# old_line_kick.net
KiCad netlist of a schematic drawn in EAGLE
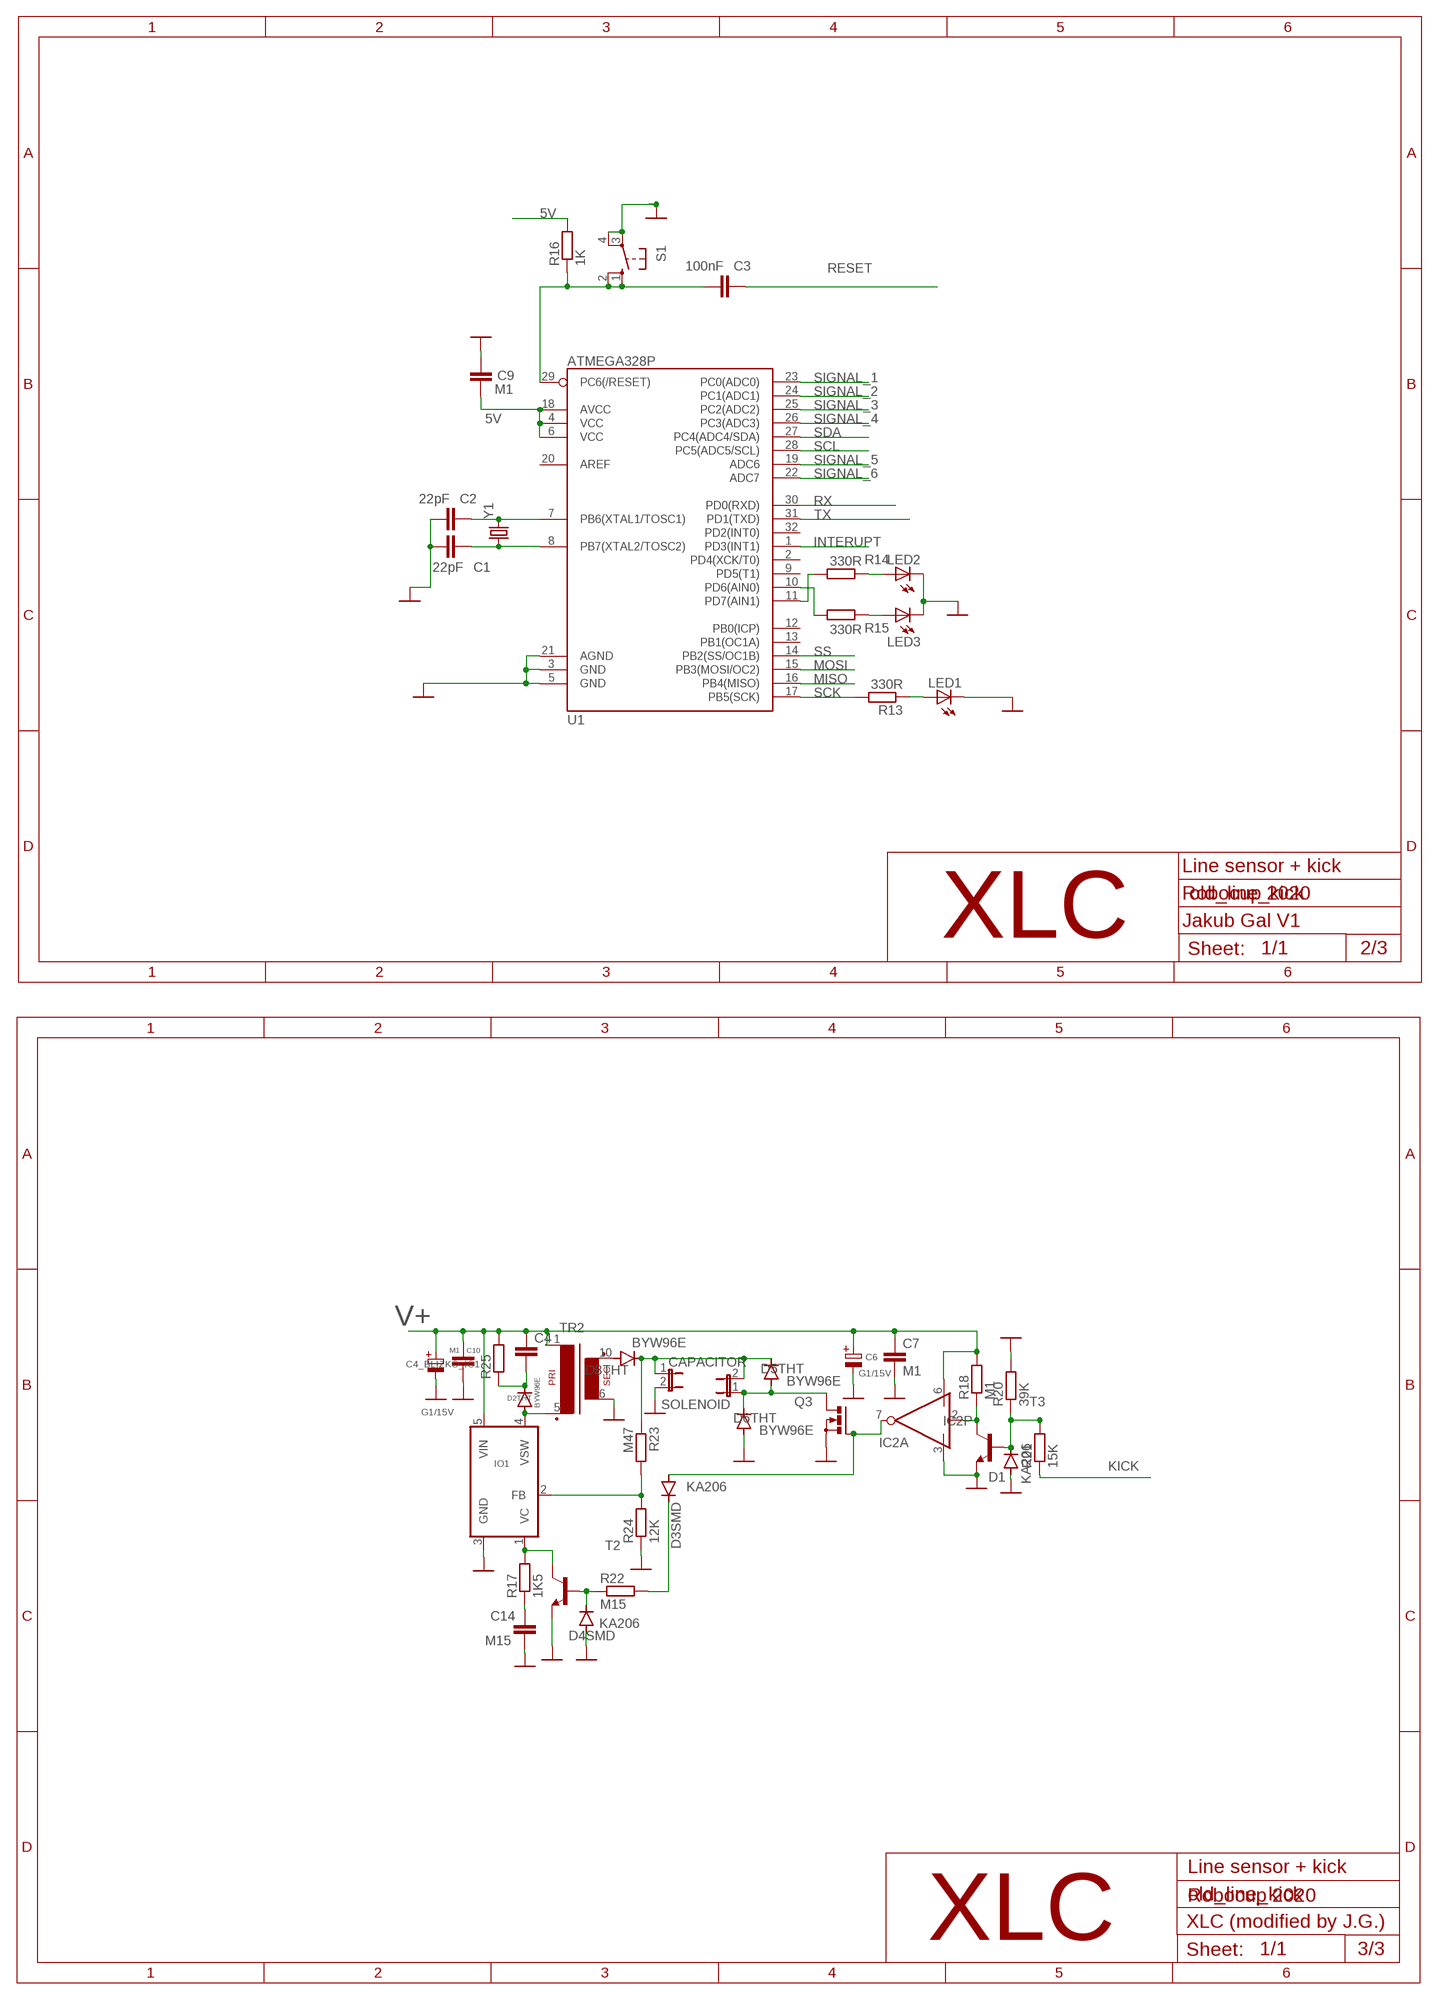
[diagram p0: schematic, sheet 1, part 1 of 2]
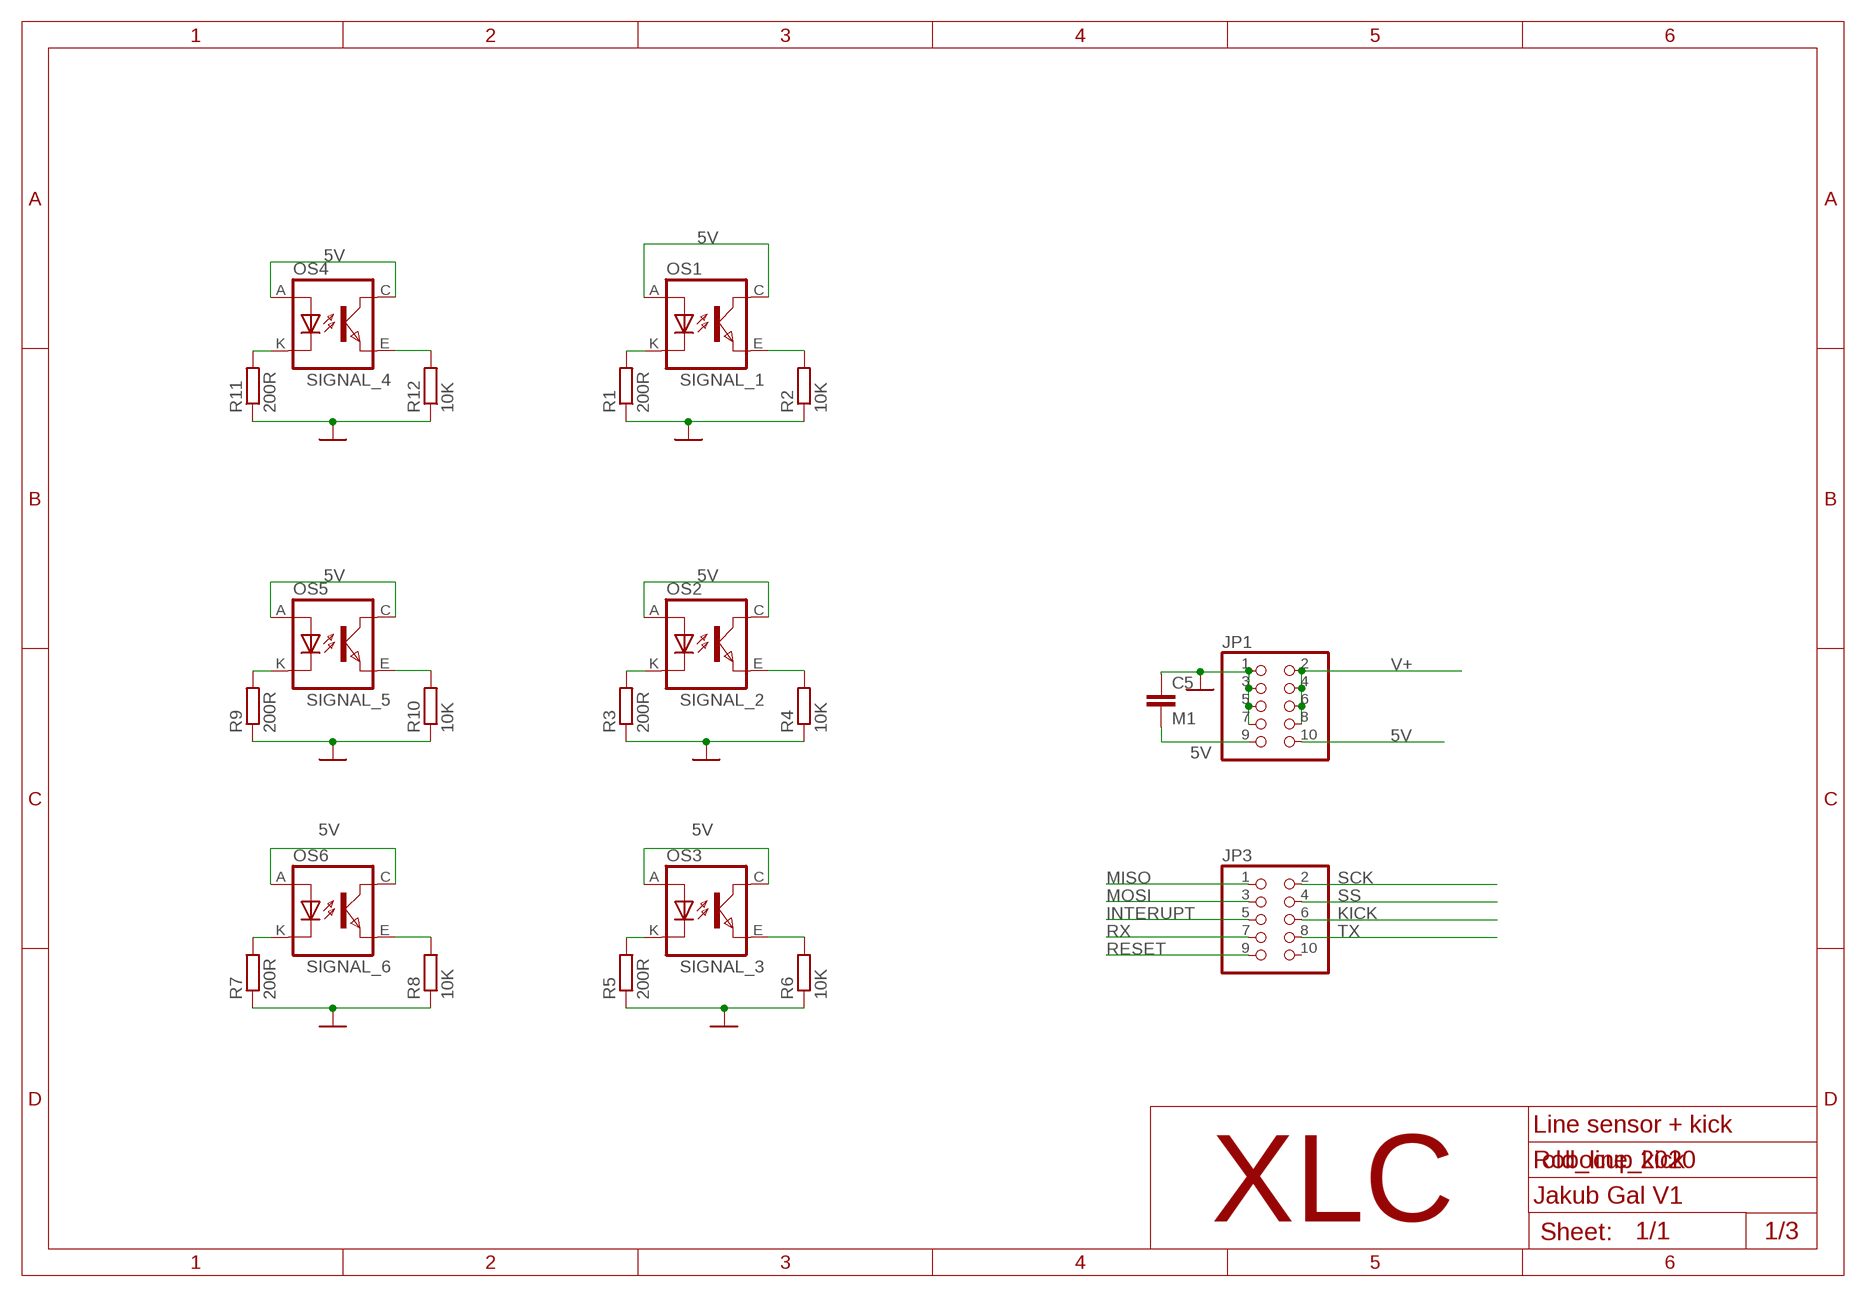
[diagram p1: schematic, sheet 1, part 2 of 2]

(export (version "E")
  (design (tool "Eeschema 10.0.6"))
  (components
    (comp (ref "C1")
      (value "22pF")
      (footprint "eagle-import:C0603")
      (libsource (lib "eagle-import") (part "rcl@1_C-EUC0603"))
    )
    (comp (ref "C2")
      (value "22pF")
      (footprint "eagle-import:C0603")
      (libsource (lib "eagle-import") (part "rcl@1_C-EUC0603"))
    )
    (comp (ref "C3")
      (value "100nF")
      (footprint "eagle-import:C0603")
      (libsource (lib "eagle-import") (part "rcl@1_C-EUC0603"))
    )
    (comp (ref "C4")
      (value "C-EU075-052X106")
      (footprint "eagle-import:C075-052X106")
      (libsource (lib "eagle-import") (part "C-EU075-052X106"))
    )
    (comp (ref "C4_BLIZKO_IO1")
      (value "G1/15V")
      (footprint "eagle-import:E-2,5_7-RAD")
      (libsource (lib "eagle-import") (part "KOND-ELEKT-2,5/7"))
    )
    (comp (ref "C5")
      (value "M1")
      (footprint "eagle-import:C0603")
      (libsource (lib "eagle-import") (part "C-EUC0603"))
    )
    (comp (ref "C6")
      (value "G1/15V")
      (footprint "eagle-import:E-2,5_7-RAD")
      (libsource (lib "eagle-import") (part "KOND-ELEKT-2,5/7"))
    )
    (comp (ref "C7")
      (value "M1")
      (footprint "eagle-import:C0805K")
      (libsource (lib "eagle-import") (part "resistor_C-EUC0805K"))
    )
    (comp (ref "C9")
      (value "M1")
      (footprint "eagle-import:C0603")
      (libsource (lib "eagle-import") (part "rcl@1_C-EUC0603"))
    )
    (comp (ref "C10")
      (value "M1")
      (footprint "eagle-import:C0805K")
      (libsource (lib "eagle-import") (part "resistor_C-EUC0805K"))
    )
    (comp (ref "C14")
      (value "M15")
      (footprint "eagle-import:C0805K")
      (libsource (lib "eagle-import") (part "resistor_C-EUC0805K"))
    )
    (comp (ref "CAPACITOR")
      (value "JP1E")
      (footprint "eagle-import:JP1")
      (libsource (lib "eagle-import") (part "JP1E"))
    )
    (comp (ref "D1")
      (value "KA206")
      (footprint "eagle-import:D-7.5")
      (libsource (lib "eagle-import") (part "DIODE-D-7.5"))
    )
    (comp (ref "D2THT")
      (value "BYW96E")
      (footprint "eagle-import:SOD64-10")
      (libsource (lib "eagle-import") (part "BYW96"))
    )
    (comp (ref "D3SMD")
      (value "KA206")
      (footprint "eagle-import:D-7.5")
      (libsource (lib "eagle-import") (part "DIODE-D-7.5"))
    )
    (comp (ref "D4SMD")
      (value "KA206")
      (footprint "eagle-import:D-7.5")
      (libsource (lib "eagle-import") (part "DIODE-D-7.5"))
    )
    (comp (ref "D5THT")
      (value "BYW96E")
      (footprint "eagle-import:SOD64-10")
      (libsource (lib "eagle-import") (part "BYW96"))
    )
    (comp (ref "D6THT")
      (value "BYW96E")
      (footprint "eagle-import:SOD64-10")
      (libsource (lib "eagle-import") (part "BYW96"))
    )
    (comp (ref "D8THT")
      (value "BYW96E")
      (footprint "eagle-import:SOD64-10")
      (libsource (lib "eagle-import") (part "BYW96"))
    )
    (comp (ref "IC2")
      (value "MIC4423BM")
      (footprint "eagle-import:SO08")
      (libsource (lib "eagle-import") (part "MIC4423BM"))
    )
    (comp (ref "IO1")
      (value "LT1071V")
      (footprint "eagle-import:TO220-5P")
      (libsource (lib "eagle-import") (part "LT1071V"))
    )
    (comp (ref "JP1")
      (value "PINHD-2X5IDC")
      (footprint "eagle-import:2X05_IDC")
      (libsource (lib "eagle-import") (part "PINHD-2X5IDC"))
    )
    (comp (ref "JP3")
      (value "PINHD-2X5IDC")
      (footprint "eagle-import:2X05_IDC")
      (libsource (lib "eagle-import") (part "PINHD-2X5IDC"))
    )
    (comp (ref "LED1")
      (value "LEDCHIPLED_0603")
      (footprint "eagle-import:CHIPLED_0603")
      (libsource (lib "eagle-import") (part "LEDCHIPLED_0603"))
    )
    (comp (ref "LED2")
      (value "LEDCHIPLED_0603")
      (footprint "eagle-import:CHIPLED_0603")
      (libsource (lib "eagle-import") (part "LEDCHIPLED_0603"))
    )
    (comp (ref "LED3")
      (value "LEDCHIPLED_0603")
      (footprint "eagle-import:CHIPLED_0603")
      (libsource (lib "eagle-import") (part "LEDCHIPLED_0603"))
    )
    (comp (ref "OS1")
      (value "TCRT5000")
      (footprint "eagle-import:TCRT5000")
      (libsource (lib "eagle-import") (part "TCRT5000"))
    )
    (comp (ref "OS2")
      (value "TCRT5000")
      (footprint "eagle-import:TCRT5000")
      (libsource (lib "eagle-import") (part "TCRT5000"))
    )
    (comp (ref "OS3")
      (value "TCRT5000")
      (footprint "eagle-import:TCRT5000")
      (libsource (lib "eagle-import") (part "TCRT5000"))
    )
    (comp (ref "OS4")
      (value "TCRT5000")
      (footprint "eagle-import:TCRT5000")
      (fields (field (name "SPICEPREFIX") "O"))
      (libsource (lib "eagle-import") (part "TCRT5000"))
    )
    (comp (ref "OS5")
      (value "TCRT5000")
      (footprint "eagle-import:TCRT5000")
      (libsource (lib "eagle-import") (part "TCRT5000"))
    )
    (comp (ref "OS6")
      (value "TCRT5000")
      (footprint "eagle-import:TCRT5000")
      (fields (field (name "SPICEPREFIX") "O"))
      (libsource (lib "eagle-import") (part "TCRT5000"))
    )
    (comp (ref "Q3")
      (value "PMOSFET_NTO220BV")
      (footprint "eagle-import:TO220BV")
      (libsource (lib "eagle-import") (part "PMOSFET_NTO220BV"))
    )
    (comp (ref "R1")
      (value "200R")
      (footprint "eagle-import:R0603")
      (libsource (lib "eagle-import") (part "R-EU_R0603"))
    )
    (comp (ref "R2")
      (value "10K")
      (footprint "eagle-import:R0603")
      (libsource (lib "eagle-import") (part "R-EU_R0603"))
    )
    (comp (ref "R3")
      (value "200R")
      (footprint "eagle-import:R0603")
      (libsource (lib "eagle-import") (part "R-EU_R0603"))
    )
    (comp (ref "R4")
      (value "10K")
      (footprint "eagle-import:R0603")
      (libsource (lib "eagle-import") (part "R-EU_R0603"))
    )
    (comp (ref "R5")
      (value "200R")
      (footprint "eagle-import:R0603")
      (libsource (lib "eagle-import") (part "R-EU_R0603"))
    )
    (comp (ref "R6")
      (value "10K")
      (footprint "eagle-import:R0603")
      (libsource (lib "eagle-import") (part "R-EU_R0603"))
    )
    (comp (ref "R7")
      (value "200R")
      (footprint "eagle-import:R0603")
      (libsource (lib "eagle-import") (part "R-EU_R0603"))
    )
    (comp (ref "R8")
      (value "10K")
      (footprint "eagle-import:R0603")
      (libsource (lib "eagle-import") (part "R-EU_R0603"))
    )
    (comp (ref "R9")
      (value "200R")
      (footprint "eagle-import:R0603")
      (libsource (lib "eagle-import") (part "R-EU_R0603"))
    )
    (comp (ref "R10")
      (value "10K")
      (footprint "eagle-import:R0603")
      (libsource (lib "eagle-import") (part "R-EU_R0603"))
    )
    (comp (ref "R11")
      (value "200R")
      (footprint "eagle-import:R0603")
      (libsource (lib "eagle-import") (part "R-EU_R0603"))
    )
    (comp (ref "R12")
      (value "10K")
      (footprint "eagle-import:R0603")
      (libsource (lib "eagle-import") (part "R-EU_R0603"))
    )
    (comp (ref "R13")
      (value "330R")
      (footprint "eagle-import:R0603")
      (libsource (lib "eagle-import") (part "R-EU_R0603"))
    )
    (comp (ref "R14")
      (value "330R")
      (footprint "eagle-import:R0603")
      (libsource (lib "eagle-import") (part "R-EU_R0603"))
    )
    (comp (ref "R15")
      (value "330R")
      (footprint "eagle-import:R0603")
      (libsource (lib "eagle-import") (part "R-EU_R0603"))
    )
    (comp (ref "R16")
      (value "1K")
      (footprint "eagle-import:R0603")
      (libsource (lib "eagle-import") (part "R-EU_R0603"))
    )
    (comp (ref "R17")
      (value "1K5")
      (footprint "eagle-import:R1206")
      (libsource (lib "eagle-import") (part "R-EU_R1206"))
    )
    (comp (ref "R18")
      (value "M1")
      (footprint "eagle-import:R1206")
      (libsource (lib "eagle-import") (part "R-EU_R1206"))
    )
    (comp (ref "R20")
      (value "39K")
      (footprint "eagle-import:R1206")
      (libsource (lib "eagle-import") (part "R-EU_R1206"))
    )
    (comp (ref "R21")
      (value "15K")
      (footprint "eagle-import:R1206")
      (libsource (lib "eagle-import") (part "R-EU_R1206"))
    )
    (comp (ref "R22")
      (value "M15")
      (footprint "eagle-import:R1206")
      (libsource (lib "eagle-import") (part "R-EU_R1206"))
    )
    (comp (ref "R23")
      (value "M47")
      (footprint "eagle-import:R1206")
      (libsource (lib "eagle-import") (part "R-EU_R1206"))
    )
    (comp (ref "R24")
      (value "12K")
      (footprint "eagle-import:R1206")
      (libsource (lib "eagle-import") (part "R-EU_R1206"))
    )
    (comp (ref "R25")
      (value "REZISTOR-7,5MM-HORIZ")
      (footprint "eagle-import:R-7,5H")
      (libsource (lib "eagle-import") (part "REZISTOR-7,5MM-HORIZ"))
    )
    (comp (ref "S1")
      (value "10-XX")
      (footprint "eagle-import:B3F-10XX")
      (fields (field (name "MPN") "B3F-1000"))
      (libsource (lib "eagle-import") (part "10-XX"))
    )
    (comp (ref "SOLENOID")
      (value "JP1E")
      (footprint "eagle-import:JP1")
      (libsource (lib "eagle-import") (part "JP1E"))
    )
    (comp (ref "T2")
      (value "-NPN-SC59-BEC")
      (footprint "eagle-import:SC59-BEC")
      (libsource (lib "eagle-import") (part "-NPN-SC59-BEC"))
    )
    (comp (ref "T3")
      (value "-NPN-SC59-BEC")
      (footprint "eagle-import:SC59-BEC")
      (libsource (lib "eagle-import") (part "-NPN-SC59-BEC"))
    )
    (comp (ref "TR2")
      (value "TRAFO-E10-R\"\"")
      (footprint "eagle-import:TRAFO-EE17X20")
      (libsource (lib "eagle-import") (part "TRAFO-E10-R{dblquote}{dblquote}"))
    )
    (comp (ref "U1")
      (value "ATMEGA328P")
      (footprint "eagle-import:TQFP32-08")
      (libsource (lib "eagle-import") (part "ATMEGA328_SMT"))
    )
    (comp (ref "Y1")
      (value "CRYSTALHC49US")
      (footprint "eagle-import:HC49US")
      (libsource (lib "eagle-import") (part "CRYSTALHC49US"))
    )
  )
  (nets
    (net (code "1") (name "/5V") (class "Default")
      (node (ref "C5") (pin "2") (pinfunction "2_2") (pintype "passive"))
      (node (ref "C9") (pin "1") (pinfunction "1_1") (pintype "passive"))
      (node (ref "JP1") (pin "10") (pinfunction "10_10") (pintype "passive"))
      (node (ref "JP1") (pin "9") (pinfunction "9_9") (pintype "passive"))
      (node (ref "OS1") (pin "A") (pinfunction "ANODE_A") (pintype "passive"))
      (node (ref "OS1") (pin "C") (pinfunction "COLLECTOR_C") (pintype "passive"))
      (node (ref "OS2") (pin "A") (pinfunction "ANODE_A") (pintype "passive"))
      (node (ref "OS2") (pin "C") (pinfunction "COLLECTOR_C") (pintype "passive"))
      (node (ref "OS3") (pin "A") (pinfunction "ANODE_A") (pintype "passive"))
      (node (ref "OS3") (pin "C") (pinfunction "COLLECTOR_C") (pintype "passive"))
      (node (ref "OS4") (pin "A") (pinfunction "ANODE_A") (pintype "passive"))
      (node (ref "OS4") (pin "C") (pinfunction "COLLECTOR_C") (pintype "passive"))
      (node (ref "OS5") (pin "A") (pinfunction "ANODE_A") (pintype "passive"))
      (node (ref "OS5") (pin "C") (pinfunction "COLLECTOR_C") (pintype "passive"))
      (node (ref "OS6") (pin "A") (pinfunction "ANODE_A") (pintype "passive"))
      (node (ref "OS6") (pin "C") (pinfunction "COLLECTOR_C") (pintype "passive"))
      (node (ref "R16") (pin "2") (pinfunction "2_2") (pintype "passive"))
      (node (ref "U1") (pin "18") (pinfunction "AVCC_18") (pintype "bidirectional"))
      (node (ref "U1") (pin "4") (pinfunction "VCC_4") (pintype "bidirectional"))
      (node (ref "U1") (pin "6") (pinfunction "VCC_6") (pintype "bidirectional"))
    )
    (net (code "2") (name "/INTERUPT") (class "Default")
      (node (ref "JP3") (pin "5") (pinfunction "5_5") (pintype "passive"))
      (node (ref "U1") (pin "1") (pinfunction "PD3(INT1)_1") (pintype "bidirectional"))
    )
    (net (code "3") (name "/KICK") (class "Default")
      (node (ref "JP3") (pin "6") (pinfunction "6_6") (pintype "passive"))
      (node (ref "R21") (pin "1") (pinfunction "1_1") (pintype "passive"))
    )
    (net (code "4") (name "/MISO") (class "Default")
      (node (ref "JP3") (pin "1") (pinfunction "1_1") (pintype "passive"))
      (node (ref "U1") (pin "16") (pinfunction "PB4(MISO)_16") (pintype "bidirectional"))
    )
    (net (code "5") (name "/MOSI") (class "Default")
      (node (ref "JP3") (pin "3") (pinfunction "3_3") (pintype "passive"))
      (node (ref "U1") (pin "15") (pinfunction "PB3(MOSI/OC2)_15") (pintype "bidirectional"))
    )
    (net (code "6") (name "/RESET") (class "Default")
      (node (ref "C3") (pin "2") (pinfunction "2_2") (pintype "passive"))
      (node (ref "JP3") (pin "9") (pinfunction "9_9") (pintype "passive"))
    )
    (net (code "7") (name "/RX") (class "Default")
      (node (ref "JP3") (pin "7") (pinfunction "7_7") (pintype "passive"))
      (node (ref "U1") (pin "30") (pinfunction "PD0(RXD)_30") (pintype "bidirectional"))
    )
    (net (code "8") (name "/SCK") (class "Default")
      (node (ref "JP3") (pin "2") (pinfunction "2_2") (pintype "passive"))
      (node (ref "R13") (pin "2") (pinfunction "2_2") (pintype "passive"))
      (node (ref "U1") (pin "17") (pinfunction "PB5(SCK)_17") (pintype "bidirectional"))
    )
    (net (code "9") (name "/SCL") (class "Default")
      (node (ref "U1") (pin "28") (pinfunction "PC5(ADC5/SCL)_28") (pintype "bidirectional"))
    )
    (net (code "10") (name "/SDA") (class "Default")
      (node (ref "U1") (pin "27") (pinfunction "PC4(ADC4/SDA)_27") (pintype "bidirectional"))
    )
    (net (code "11") (name "/SIGNAL_1") (class "Default")
      (node (ref "OS1") (pin "E") (pinfunction "EMITTER_E") (pintype "passive"))
      (node (ref "R2") (pin "2") (pinfunction "2_2") (pintype "passive"))
      (node (ref "U1") (pin "23") (pinfunction "PC0(ADC0)_23") (pintype "bidirectional"))
    )
    (net (code "12") (name "/SIGNAL_2") (class "Default")
      (node (ref "OS2") (pin "E") (pinfunction "EMITTER_E") (pintype "passive"))
      (node (ref "R4") (pin "2") (pinfunction "2_2") (pintype "passive"))
      (node (ref "U1") (pin "24") (pinfunction "PC1(ADC1)_24") (pintype "bidirectional"))
    )
    (net (code "13") (name "/SIGNAL_3") (class "Default")
      (node (ref "OS3") (pin "E") (pinfunction "EMITTER_E") (pintype "passive"))
      (node (ref "R6") (pin "2") (pinfunction "2_2") (pintype "passive"))
      (node (ref "U1") (pin "25") (pinfunction "PC2(ADC2)_25") (pintype "bidirectional"))
    )
    (net (code "14") (name "/SIGNAL_4") (class "Default")
      (node (ref "OS4") (pin "E") (pinfunction "EMITTER_E") (pintype "passive"))
      (node (ref "R12") (pin "2") (pinfunction "2_2") (pintype "passive"))
      (node (ref "U1") (pin "26") (pinfunction "PC3(ADC3)_26") (pintype "bidirectional"))
    )
    (net (code "15") (name "/SIGNAL_5") (class "Default")
      (node (ref "OS5") (pin "E") (pinfunction "EMITTER_E") (pintype "passive"))
      (node (ref "R10") (pin "2") (pinfunction "2_2") (pintype "passive"))
      (node (ref "U1") (pin "19") (pinfunction "ADC6_19") (pintype "bidirectional"))
    )
    (net (code "16") (name "/SIGNAL_6") (class "Default")
      (node (ref "OS6") (pin "E") (pinfunction "EMITTER_E") (pintype "passive"))
      (node (ref "R8") (pin "2") (pinfunction "2_2") (pintype "passive"))
      (node (ref "U1") (pin "22") (pinfunction "ADC7_22") (pintype "bidirectional"))
    )
    (net (code "17") (name "/SS") (class "Default")
      (node (ref "JP3") (pin "4") (pinfunction "4_4") (pintype "passive"))
      (node (ref "U1") (pin "14") (pinfunction "PB2(SS/OC1B)_14") (pintype "bidirectional"))
    )
    (net (code "18") (name "/TX") (class "Default")
      (node (ref "JP3") (pin "8") (pinfunction "8_8") (pintype "passive"))
      (node (ref "U1") (pin "31") (pinfunction "PD1(TXD)_31") (pintype "bidirectional"))
    )
    (net (code "19") (name "/V+") (class "Default")
      (node (ref "C10") (pin "1") (pinfunction "1_1") (pintype "passive"))
      (node (ref "C4") (pin "1") (pinfunction "1_1") (pintype "passive"))
      (node (ref "C4_BLIZKO_IO1") (pin "+") (pinfunction "+_+") (pintype "passive"))
      (node (ref "C6") (pin "+") (pinfunction "+_+") (pintype "passive"))
      (node (ref "C7") (pin "1") (pinfunction "1_1") (pintype "passive"))
      (node (ref "IC2") (pin "6") (pinfunction "V+_6") (pintype "power_in"))
      (node (ref "IO1") (pin "5") (pinfunction "VIN_5") (pintype "power_in"))
      (node (ref "JP1") (pin "2") (pinfunction "2_2") (pintype "passive"))
      (node (ref "JP1") (pin "4") (pinfunction "4_4") (pintype "passive"))
      (node (ref "JP1") (pin "6") (pinfunction "6_6") (pintype "passive"))
      (node (ref "JP1") (pin "8") (pinfunction "8_8") (pintype "passive"))
      (node (ref "R18") (pin "2") (pinfunction "2_2") (pintype "passive"))
      (node (ref "R25") (pin "2") (pinfunction "2_2") (pintype "passive"))
      (node (ref "TR2") (pin "1") (pinfunction "1_1") (pintype "passive"))
    )
    (net (code "20") (name "GND") (class "Default")
      (node (ref "C1") (pin "1") (pinfunction "1_1") (pintype "passive"))
      (node (ref "C10") (pin "2") (pinfunction "2_2") (pintype "passive"))
      (node (ref "C14") (pin "2") (pinfunction "2_2") (pintype "passive"))
      (node (ref "C2") (pin "1") (pinfunction "1_1") (pintype "passive"))
      (node (ref "C4_BLIZKO_IO1") (pin "-") (pinfunction "-_-") (pintype "passive"))
      (node (ref "C5") (pin "1") (pinfunction "1_1") (pintype "passive"))
      (node (ref "C6") (pin "-") (pinfunction "-_-") (pintype "passive"))
      (node (ref "C7") (pin "2") (pinfunction "2_2") (pintype "passive"))
      (node (ref "C9") (pin "2") (pinfunction "2_2") (pintype "passive"))
      (node (ref "CAPACITOR") (pin "2") (pinfunction "2_2") (pintype "passive"))
      (node (ref "D1") (pin "A") (pinfunction "A_A") (pintype "passive"))
      (node (ref "D4SMD") (pin "A") (pinfunction "A_A") (pintype "passive"))
      (node (ref "D6THT") (pin "A") (pinfunction "A_A") (pintype "passive"))
      (node (ref "IC2") (pin "3") (pinfunction "GND_3") (pintype "power_in"))
      (node (ref "IO1") (pin "3") (pinfunction "GND_3") (pintype "power_in"))
      (node (ref "JP1") (pin "1") (pinfunction "1_1") (pintype "passive"))
      (node (ref "JP1") (pin "3") (pinfunction "3_3") (pintype "passive"))
      (node (ref "JP1") (pin "5") (pinfunction "5_5") (pintype "passive"))
      (node (ref "JP1") (pin "7") (pinfunction "7_7") (pintype "passive"))
      (node (ref "LED1") (pin "C") (pinfunction "C_C") (pintype "passive"))
      (node (ref "LED2") (pin "C") (pinfunction "C_C") (pintype "passive"))
      (node (ref "LED3") (pin "C") (pinfunction "C_C") (pintype "passive"))
      (node (ref "Q3") (pin "S") (pinfunction "S_S") (pintype "passive"))
      (node (ref "R1") (pin "1") (pinfunction "1_1") (pintype "passive"))
      (node (ref "R10") (pin "1") (pinfunction "1_1") (pintype "passive"))
      (node (ref "R11") (pin "1") (pinfunction "1_1") (pintype "passive"))
      (node (ref "R12") (pin "1") (pinfunction "1_1") (pintype "passive"))
      (node (ref "R2") (pin "1") (pinfunction "1_1") (pintype "passive"))
      (node (ref "R20") (pin "2") (pinfunction "2_2") (pintype "passive"))
      (node (ref "R24") (pin "1") (pinfunction "1_1") (pintype "passive"))
      (node (ref "R3") (pin "1") (pinfunction "1_1") (pintype "passive"))
      (node (ref "R4") (pin "1") (pinfunction "1_1") (pintype "passive"))
      (node (ref "R5") (pin "1") (pinfunction "1_1") (pintype "passive"))
      (node (ref "R6") (pin "1") (pinfunction "1_1") (pintype "passive"))
      (node (ref "R7") (pin "1") (pinfunction "1_1") (pintype "passive"))
      (node (ref "R8") (pin "1") (pinfunction "1_1") (pintype "passive"))
      (node (ref "R9") (pin "1") (pinfunction "1_1") (pintype "passive"))
      (node (ref "S1") (pin "3") (pinfunction "P_3") (pintype "passive"))
      (node (ref "S1") (pin "4") (pinfunction "P1_4") (pintype "passive"))
      (node (ref "T2") (pin "E") (pinfunction "E_E") (pintype "passive"))
      (node (ref "T3") (pin "E") (pinfunction "E_E") (pintype "passive"))
      (node (ref "TR2") (pin "6") (pinfunction "3_6") (pintype "passive"))
      (node (ref "U1") (pin "21") (pinfunction "AGND_21") (pintype "bidirectional"))
      (node (ref "U1") (pin "3") (pinfunction "GND_3") (pintype "bidirectional"))
      (node (ref "U1") (pin "5") (pinfunction "GND_5") (pintype "bidirectional"))
    )
    (net (code "21") (name "Net-(C4-Pad2)") (class "Default")
      (node (ref "C4") (pin "2") (pinfunction "2_2") (pintype "passive"))
      (node (ref "D2THT") (pin "C") (pinfunction "C_C") (pintype "passive"))
      (node (ref "R25") (pin "1") (pinfunction "1_1") (pintype "passive"))
    )
    (net (code "22") (name "Net-(C14-Pad1)") (class "Default")
      (node (ref "C14") (pin "1") (pinfunction "1_1") (pintype "passive"))
      (node (ref "R17") (pin "1") (pinfunction "1_1") (pintype "passive"))
    )
    (net (code "23") (name "Net-(CAPACITOR-Pad1)") (class "Default")
      (node (ref "CAPACITOR") (pin "1") (pinfunction "1_1") (pintype "passive"))
      (node (ref "D5THT") (pin "C") (pinfunction "C_C") (pintype "passive"))
      (node (ref "D8THT") (pin "C") (pinfunction "C_C") (pintype "passive"))
      (node (ref "R23") (pin "1") (pinfunction "1_1") (pintype "passive"))
      (node (ref "SOLENOID") (pin "2") (pinfunction "2_2") (pintype "passive"))
    )
    (net (code "24") (name "Net-(D1-PadC)") (class "Default")
      (node (ref "D1") (pin "C") (pinfunction "C_C") (pintype "passive"))
      (node (ref "R20") (pin "1") (pinfunction "1_1") (pintype "passive"))
      (node (ref "R21") (pin "2") (pinfunction "2_2") (pintype "passive"))
      (node (ref "T3") (pin "B") (pinfunction "B_B") (pintype "passive"))
    )
    (net (code "25") (name "Net-(D3SMD-PadC)") (class "Default")
      (node (ref "D3SMD") (pin "C") (pinfunction "C_C") (pintype "passive"))
      (node (ref "R22") (pin "2") (pinfunction "2_2") (pintype "passive"))
    )
    (net (code "26") (name "Net-(D4SMD-PadC)") (class "Default")
      (node (ref "D4SMD") (pin "C") (pinfunction "C_C") (pintype "passive"))
      (node (ref "R22") (pin "1") (pinfunction "1_1") (pintype "passive"))
      (node (ref "T2") (pin "B") (pinfunction "B_B") (pintype "passive"))
    )
    (net (code "27") (name "Net-(D5THT-PadA)") (class "Default")
      (node (ref "D5THT") (pin "A") (pinfunction "A_A") (pintype "passive"))
      (node (ref "D6THT") (pin "C") (pinfunction "C_C") (pintype "passive"))
      (node (ref "Q3") (pin "D") (pinfunction "D_D") (pintype "passive"))
      (node (ref "SOLENOID") (pin "1") (pinfunction "1_1") (pintype "passive"))
    )
    (net (code "28") (name "Net-(IC2A-IN)") (class "Default")
      (node (ref "IC2") (pin "2") (pinfunction "IN_2") (pintype "input"))
      (node (ref "R18") (pin "1") (pinfunction "1_1") (pintype "passive"))
      (node (ref "T3") (pin "C") (pinfunction "C_C") (pintype "passive"))
    )
    (net (code "29") (name "Net-(IC2A-OUT)") (class "Default")
      (node (ref "D3SMD") (pin "A") (pinfunction "A_A") (pintype "passive"))
      (node (ref "IC2") (pin "7") (pinfunction "OUT_7") (pintype "output"))
      (node (ref "Q3") (pin "G") (pinfunction "G_G") (pintype "passive"))
    )
    (net (code "30") (name "Net-(IO1-FB)") (class "Default")
      (node (ref "IO1") (pin "2") (pinfunction "FB_2") (pintype "input"))
      (node (ref "R23") (pin "2") (pinfunction "2_2") (pintype "passive"))
      (node (ref "R24") (pin "2") (pinfunction "2_2") (pintype "passive"))
    )
    (net (code "31") (name "Net-(IO1-VC)") (class "Default")
      (node (ref "IO1") (pin "1") (pinfunction "VC_1") (pintype "input"))
      (node (ref "R17") (pin "2") (pinfunction "2_2") (pintype "passive"))
      (node (ref "T2") (pin "C") (pinfunction "C_C") (pintype "passive"))
    )
    (net (code "32") (name "Net-(IO1-VSW)") (class "Default")
      (node (ref "D2THT") (pin "A") (pinfunction "A_A") (pintype "passive"))
      (node (ref "IO1") (pin "4") (pinfunction "VSW_4") (pintype "output"))
      (node (ref "TR2") (pin "5") (pinfunction "2_5") (pintype "passive"))
    )
    (net (code "33") (name "Net-(LED1-PadA)") (class "Default")
      (node (ref "LED1") (pin "A") (pinfunction "A_A") (pintype "passive"))
      (node (ref "R13") (pin "1") (pinfunction "1_1") (pintype "passive"))
    )
    (net (code "34") (name "Net-(LED2-PadA)") (class "Default")
      (node (ref "LED2") (pin "A") (pinfunction "A_A") (pintype "passive"))
      (node (ref "R14") (pin "1") (pinfunction "1_1") (pintype "passive"))
    )
    (net (code "35") (name "Net-(LED3-PadA)") (class "Default")
      (node (ref "LED3") (pin "A") (pinfunction "A_A") (pintype "passive"))
      (node (ref "R15") (pin "1") (pinfunction "1_1") (pintype "passive"))
    )
    (net (code "36") (name "Net-(OS1-CATHODE)") (class "Default")
      (node (ref "OS1") (pin "K") (pinfunction "CATHODE_K") (pintype "passive"))
      (node (ref "R1") (pin "2") (pinfunction "2_2") (pintype "passive"))
    )
    (net (code "37") (name "Net-(OS2-CATHODE)") (class "Default")
      (node (ref "OS2") (pin "K") (pinfunction "CATHODE_K") (pintype "passive"))
      (node (ref "R3") (pin "2") (pinfunction "2_2") (pintype "passive"))
    )
    (net (code "38") (name "Net-(OS3-CATHODE)") (class "Default")
      (node (ref "OS3") (pin "K") (pinfunction "CATHODE_K") (pintype "passive"))
      (node (ref "R5") (pin "2") (pinfunction "2_2") (pintype "passive"))
    )
    (net (code "39") (name "Net-(OS4-CATHODE)") (class "Default")
      (node (ref "OS4") (pin "K") (pinfunction "CATHODE_K") (pintype "passive"))
      (node (ref "R11") (pin "2") (pinfunction "2_2") (pintype "passive"))
    )
    (net (code "40") (name "Net-(OS5-CATHODE)") (class "Default")
      (node (ref "OS5") (pin "K") (pinfunction "CATHODE_K") (pintype "passive"))
      (node (ref "R9") (pin "2") (pinfunction "2_2") (pintype "passive"))
    )
    (net (code "41") (name "Net-(OS6-CATHODE)") (class "Default")
      (node (ref "OS6") (pin "K") (pinfunction "CATHODE_K") (pintype "passive"))
      (node (ref "R7") (pin "2") (pinfunction "2_2") (pintype "passive"))
    )
    (net (code "42") (name "Net-(S1-S)") (class "Default")
      (node (ref "C3") (pin "1") (pinfunction "1_1") (pintype "passive"))
      (node (ref "R16") (pin "1") (pinfunction "1_1") (pintype "passive"))
      (node (ref "S1") (pin "1") (pinfunction "S_1") (pintype "passive"))
      (node (ref "S1") (pin "2") (pinfunction "S1_2") (pintype "passive"))
      (node (ref "U1") (pin "29") (pinfunction "PC6(/RESET)_29") (pintype "bidirectional"))
    )
    (net (code "43") (name "Net-(TR2-4)") (class "Default")
      (node (ref "D8THT") (pin "A") (pinfunction "A_A") (pintype "passive"))
      (node (ref "TR2") (pin "10") (pinfunction "4_10") (pintype "passive"))
    )
    (net (code "44") (name "Net-(U1-PB6(XTAL1{slash}TOSC1))") (class "Default")
      (node (ref "C2") (pin "2") (pinfunction "2_2") (pintype "passive"))
      (node (ref "U1") (pin "7") (pinfunction "PB6(XTAL1/TOSC1)_7") (pintype "bidirectional"))
      (node (ref "Y1") (pin "2") (pinfunction "2_2") (pintype "passive"))
    )
    (net (code "45") (name "Net-(U1-PB7(XTAL2{slash}TOSC2))") (class "Default")
      (node (ref "C1") (pin "2") (pinfunction "2_2") (pintype "passive"))
      (node (ref "U1") (pin "8") (pinfunction "PB7(XTAL2/TOSC2)_8") (pintype "bidirectional"))
      (node (ref "Y1") (pin "1") (pinfunction "1_1") (pintype "passive"))
    )
    (net (code "46") (name "Net-(U1-PD6(AIN0))") (class "Default")
      (node (ref "R15") (pin "2") (pinfunction "2_2") (pintype "passive"))
      (node (ref "U1") (pin "10") (pinfunction "PD6(AIN0)_10") (pintype "bidirectional"))
    )
    (net (code "47") (name "Net-(U1-PD7(AIN1))") (class "Default")
      (node (ref "R14") (pin "2") (pinfunction "2_2") (pintype "passive"))
      (node (ref "U1") (pin "11") (pinfunction "PD7(AIN1)_11") (pintype "bidirectional"))
    )
    (net (code "48") (name "unconnected-(JP3-Pad10)") (class "Default")
      (node (ref "JP3") (pin "10") (pinfunction "10_10") (pintype "passive"))
    )
    (net (code "49") (name "unconnected-(U1-AREF-Pad20)") (class "Default")
      (node (ref "U1") (pin "20") (pinfunction "AREF_20") (pintype "bidirectional"))
    )
    (net (code "50") (name "unconnected-(U1-PB0(ICP)-Pad12)") (class "Default")
      (node (ref "U1") (pin "12") (pinfunction "PB0(ICP)_12") (pintype "bidirectional"))
    )
    (net (code "51") (name "unconnected-(U1-PB1(OC1A)-Pad13)") (class "Default")
      (node (ref "U1") (pin "13") (pinfunction "PB1(OC1A)_13") (pintype "bidirectional"))
    )
    (net (code "52") (name "unconnected-(U1-PD2(INT0)-Pad32)") (class "Default")
      (node (ref "U1") (pin "32") (pinfunction "PD2(INT0)_32") (pintype "bidirectional"))
    )
    (net (code "53") (name "unconnected-(U1-PD4(XCK{slash}T0)-Pad2)") (class "Default")
      (node (ref "U1") (pin "2") (pinfunction "PD4(XCK/T0)_2") (pintype "bidirectional"))
    )
    (net (code "54") (name "unconnected-(U1-PD5(T1)-Pad9)") (class "Default")
      (node (ref "U1") (pin "9") (pinfunction "PD5(T1)_9") (pintype "bidirectional"))
    )
  )
)
